# ExternalLEDsSUPERSMALL.net
KiCad netlist of a schematic drawn in EAGLE
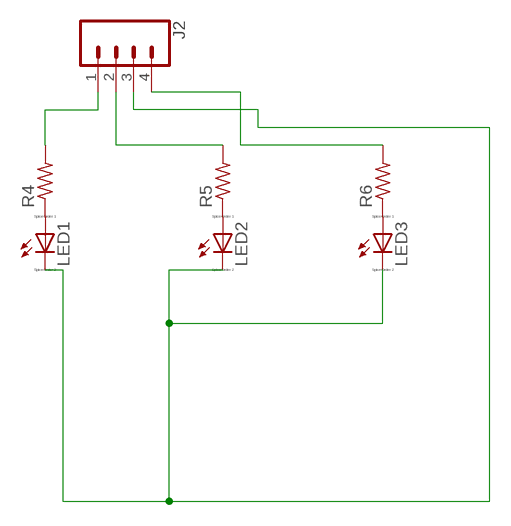
[diagram p0: schematic, sheet 1]

(export (version "E")
  (design (tool "Eeschema 10.0.6"))
  (components
    (comp (ref "J2")
      (value "CONN_04POLAR")
      (footprint "eagle-import:MOLEX-1X4")
      (libsource (lib "eagle-import") (part "CONN_04POLAR"))
    )
    (comp (ref "LED1")
      (value "LED_E")
      (footprint "eagle-import:LED_1206")
      (libsource (lib "eagle-import") (part "LED_E"))
    )
    (comp (ref "LED2")
      (value "LED_E")
      (footprint "eagle-import:LED_1206")
      (libsource (lib "eagle-import") (part "LED_E"))
    )
    (comp (ref "LED3")
      (value "LED_E")
      (footprint "eagle-import:LED_1206")
      (libsource (lib "eagle-import") (part "LED_E"))
    )
    (comp (ref "R4")
      (value "R-US_M1206")
      (footprint "eagle-import:M1206")
      (libsource (lib "eagle-import") (part "R-US_M1206"))
    )
    (comp (ref "R5")
      (value "R-US_M1206")
      (footprint "eagle-import:M1206")
      (libsource (lib "eagle-import") (part "R-US_M1206"))
    )
    (comp (ref "R6")
      (value "R-US_M1206")
      (footprint "eagle-import:M1206")
      (libsource (lib "eagle-import") (part "R-US_M1206"))
    )
  )
  (nets
    (net (code "1") (name "Net-(J2-Pad1)") (class "Default")
      (node (ref "J2") (pin "1") (pinfunction "1_1") (pintype "passive"))
      (node (ref "R4") (pin "2") (pinfunction "2_2") (pintype "passive"))
    )
    (net (code "2") (name "Net-(J2-Pad2)") (class "Default")
      (node (ref "J2") (pin "2") (pinfunction "2_2") (pintype "passive"))
      (node (ref "R5") (pin "2") (pinfunction "2_2") (pintype "passive"))
    )
    (net (code "3") (name "Net-(J2-Pad3)") (class "Default")
      (node (ref "J2") (pin "3") (pinfunction "3_3") (pintype "passive"))
      (node (ref "LED1") (pin "C") (pinfunction "C_C") (pintype "passive"))
      (node (ref "LED2") (pin "C") (pinfunction "C_C") (pintype "passive"))
      (node (ref "LED3") (pin "C") (pinfunction "C_C") (pintype "passive"))
    )
    (net (code "4") (name "Net-(J2-Pad4)") (class "Default")
      (node (ref "J2") (pin "4") (pinfunction "4_4") (pintype "passive"))
      (node (ref "R6") (pin "2") (pinfunction "2_2") (pintype "passive"))
    )
    (net (code "5") (name "Net-(LED1-PadA)") (class "Default")
      (node (ref "LED1") (pin "A") (pinfunction "A_A") (pintype "passive"))
      (node (ref "R4") (pin "1") (pinfunction "1_1") (pintype "passive"))
    )
    (net (code "6") (name "Net-(LED2-PadA)") (class "Default")
      (node (ref "LED2") (pin "A") (pinfunction "A_A") (pintype "passive"))
      (node (ref "R5") (pin "1") (pinfunction "1_1") (pintype "passive"))
    )
    (net (code "7") (name "Net-(LED3-PadA)") (class "Default")
      (node (ref "LED3") (pin "A") (pinfunction "A_A") (pintype "passive"))
      (node (ref "R6") (pin "1") (pinfunction "1_1") (pintype "passive"))
    )
  )
)
